# PressureSensorSingle.net
KiCad netlist of a schematic drawn in EAGLE
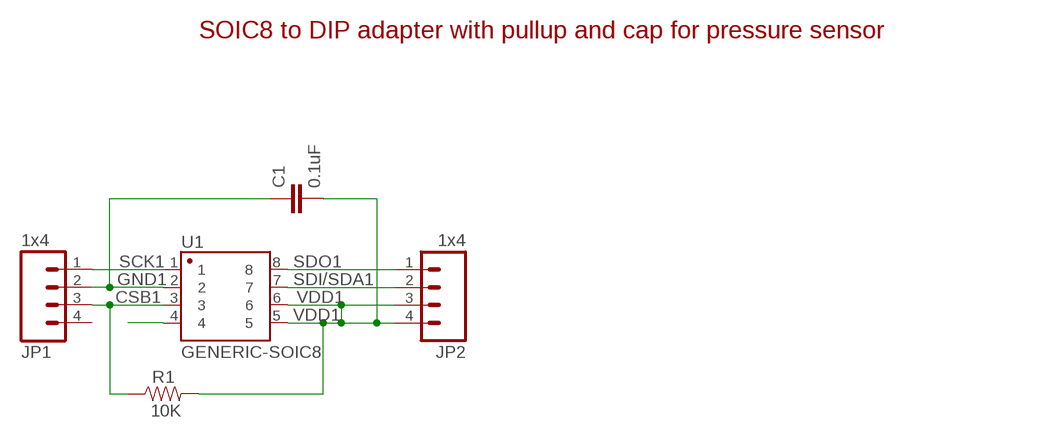
[diagram p0: schematic, sheet 1]

(export (version "E")
  (design (tool "Eeschema 10.0.6"))
  (components
    (comp (ref "C1")
      (value "0.1uF")
      (footprint "eagle-import:0603")
      (libsource (lib "eagle-import") (part "0.1UF-0603-25V-5%"))
    )
    (comp (ref "JP1")
      (value "1x4")
      (footprint "eagle-import:1X04_NO_SILK")
      (libsource (lib "eagle-import") (part "M041X04_NO_SILK"))
    )
    (comp (ref "JP2")
      (value "1x4")
      (footprint "eagle-import:1X04_NO_SILK_ALL_ROUND")
      (libsource (lib "eagle-import") (part "M04NO_SILK_ALL_ROUND"))
    )
    (comp (ref "R1")
      (value "10K")
      (footprint "eagle-import:0603")
      (libsource (lib "eagle-import") (part "RESISTOR0603"))
    )
    (comp (ref "U1")
      (value "GENERIC-SOIC8")
      (footprint "eagle-import:SO08-UNIVERSAL")
      (libsource (lib "eagle-import") (part "GENERIC-SOIC8"))
    )
  )
  (nets
    (net (code "1") (name "/CSB1") (class "Default")
      (node (ref "JP1") (pin "3") (pinfunction "3_3") (pintype "passive"))
      (node (ref "R1") (pin "1") (pinfunction "1_1") (pintype "passive"))
      (node (ref "U1") (pin "3") (pinfunction "3_3") (pintype "bidirectional"))
    )
    (net (code "2") (name "/GND1") (class "Default")
      (node (ref "C1") (pin "1") (pinfunction "1_1") (pintype "passive"))
      (node (ref "JP1") (pin "2") (pinfunction "2_2") (pintype "passive"))
      (node (ref "U1") (pin "2") (pinfunction "2_2") (pintype "bidirectional"))
    )
    (net (code "3") (name "/SCK1") (class "Default")
      (node (ref "JP1") (pin "1") (pinfunction "1_1") (pintype "passive"))
      (node (ref "U1") (pin "1") (pinfunction "1_1") (pintype "bidirectional"))
    )
    (net (code "4") (name "/SDI{slash}SDA1") (class "Default")
      (node (ref "JP2") (pin "2") (pinfunction "2_2") (pintype "passive"))
      (node (ref "U1") (pin "7") (pinfunction "7_7") (pintype "bidirectional"))
    )
    (net (code "5") (name "/SDO1") (class "Default")
      (node (ref "JP2") (pin "1") (pinfunction "1_1") (pintype "passive"))
      (node (ref "U1") (pin "8") (pinfunction "8_8") (pintype "bidirectional"))
    )
    (net (code "6") (name "/VDD1") (class "Default")
      (node (ref "C1") (pin "2") (pinfunction "2_2") (pintype "passive"))
      (node (ref "JP2") (pin "3") (pinfunction "3_3") (pintype "passive"))
      (node (ref "JP2") (pin "4") (pinfunction "4_4") (pintype "passive"))
      (node (ref "R1") (pin "2") (pinfunction "2_2") (pintype "passive"))
      (node (ref "U1") (pin "5") (pinfunction "5_5") (pintype "bidirectional"))
      (node (ref "U1") (pin "6") (pinfunction "6_6") (pintype "bidirectional"))
    )
    (net (code "7") (name "unconnected-(JP1-Pad4)") (class "Default")
      (node (ref "JP1") (pin "4") (pinfunction "4_4") (pintype "passive"))
    )
    (net (code "8") (name "unconnected-(U1-Pad4)") (class "Default")
      (node (ref "U1") (pin "4") (pinfunction "4_4") (pintype "bidirectional"))
    )
  )
)
